# Rev_B.net
KiCad netlist of a schematic drawn in EAGLE
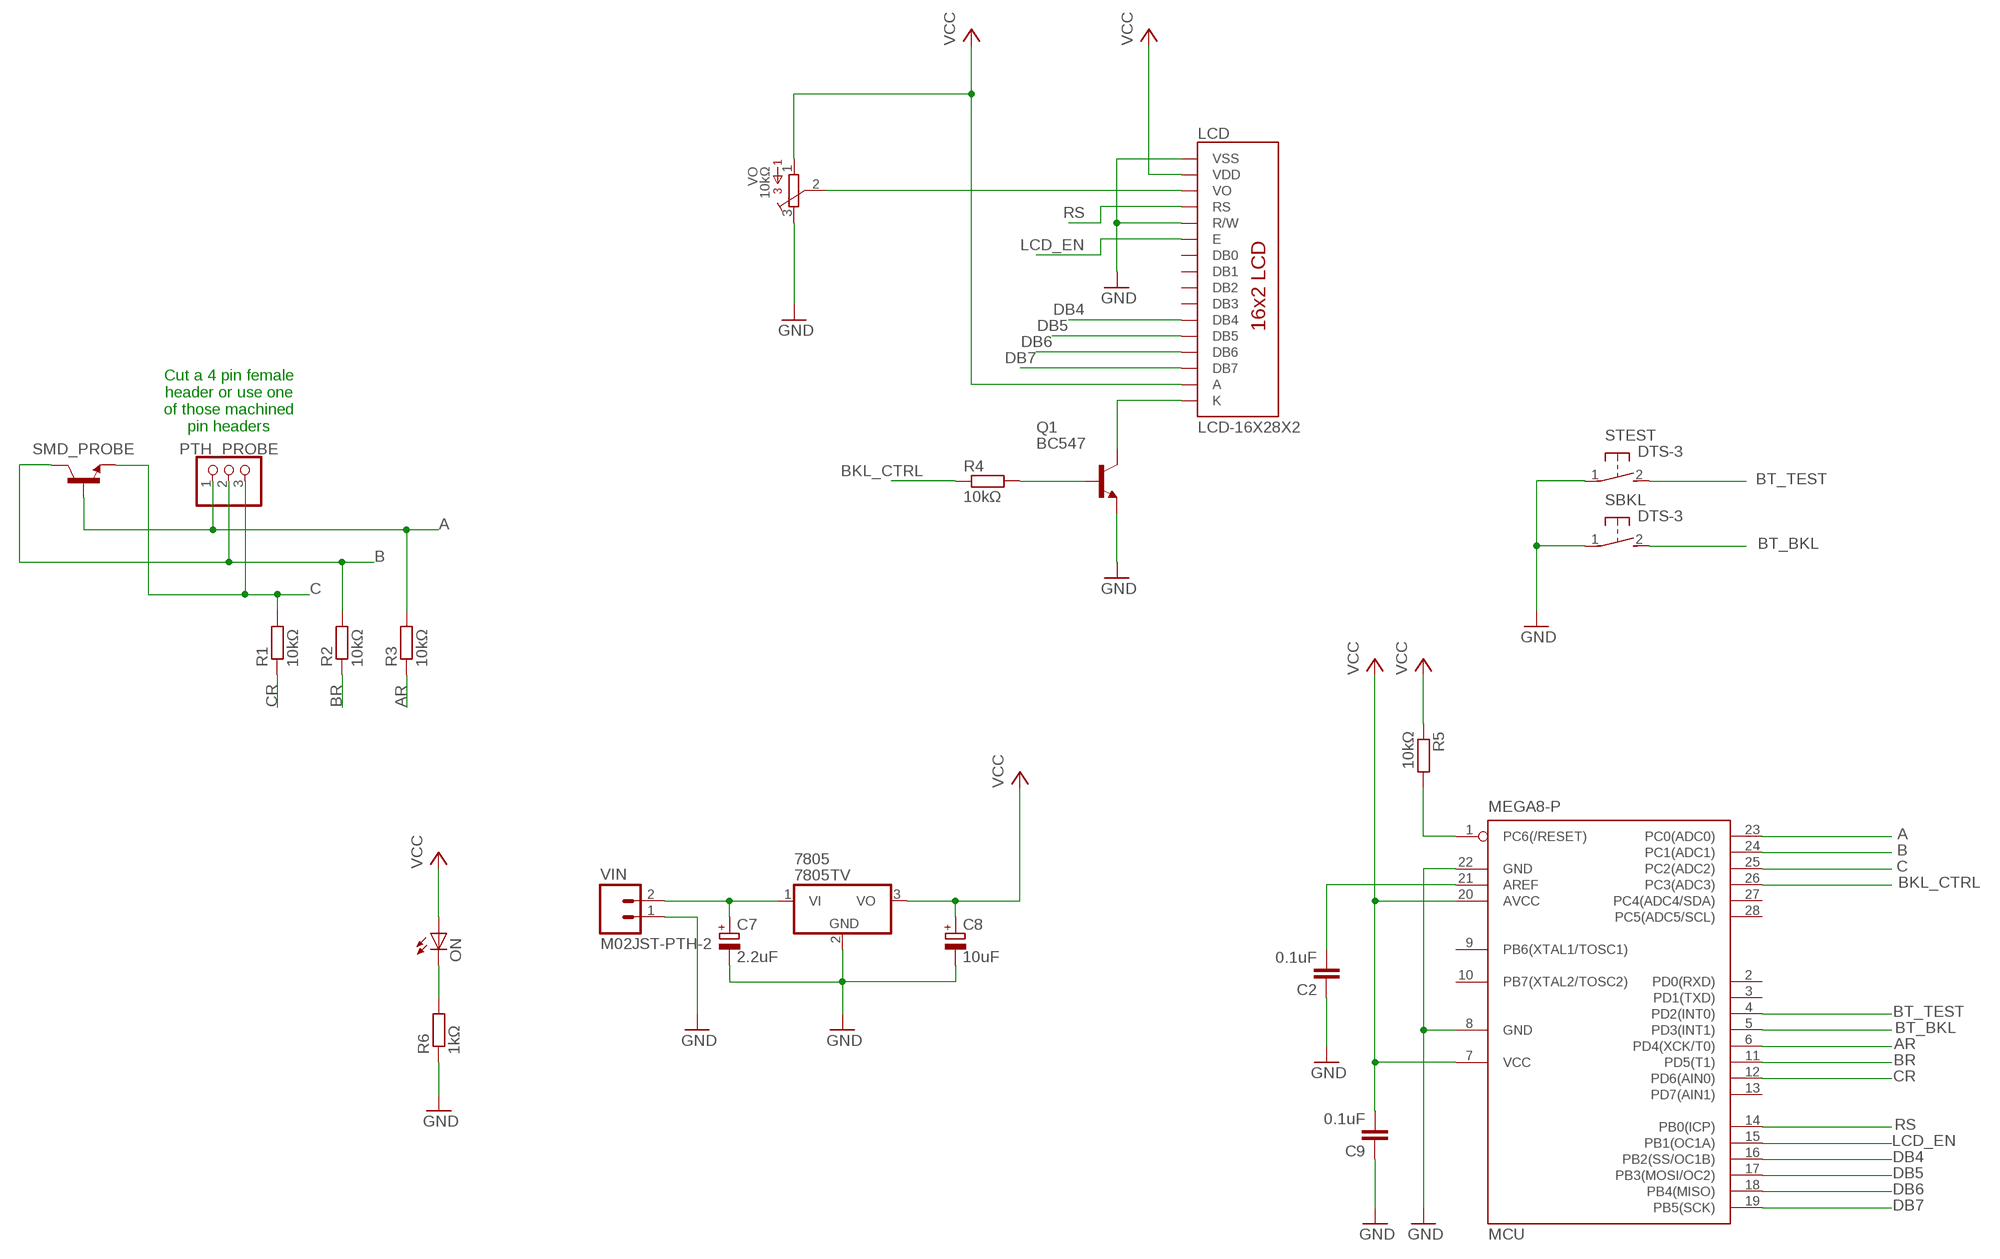
[diagram p0: schematic, sheet 1]

(export (version "E")
  (design (tool "Eeschema 10.0.6"))
  (components
    (comp (ref "7805")
      (value "7805TV")
      (footprint "eagle-import:TO220V")
      (libsource (lib "eagle-import") (part "78TV05"))
    )
    (comp (ref "C2")
      (value "0.1uF")
      (footprint "eagle-import:C025-025X050")
      (libsource (lib "eagle-import") (part "C-EU025-025X050"))
    )
    (comp (ref "C7")
      (value "2.2uF")
      (footprint "eagle-import:E2,5-6")
      (libsource (lib "eagle-import") (part "CPOL-EUE2.5-6"))
    )
    (comp (ref "C8")
      (value "10uF")
      (footprint "eagle-import:E2,5-6")
      (libsource (lib "eagle-import") (part "CPOL-EUE2.5-6"))
    )
    (comp (ref "C9")
      (value "0.1uF")
      (footprint "eagle-import:C050-025X075")
      (libsource (lib "eagle-import") (part "C-EU050-025X075"))
    )
    (comp (ref "LCD")
      (value "LCD-16X28X2")
      (footprint "eagle-import:LCD-8X2")
      (libsource (lib "eagle-import") (part "LCD-16X28X2"))
    )
    (comp (ref "MCU")
      (value "MEGA8-P")
      (footprint "eagle-import:DIL28-3")
      (libsource (lib "eagle-import") (part "MEGA8-P"))
    )
    (comp (ref "ON")
      (value "LED3MM")
      (footprint "eagle-import:LED3MM")
      (libsource (lib "eagle-import") (part "LED3MM"))
    )
    (comp (ref "PTH_PROBE")
      (value "PINHD-1X3")
      (footprint "eagle-import:1X03")
      (libsource (lib "eagle-import") (part "PINHD-1X3"))
    )
    (comp (ref "Q1")
      (value "BC547")
      (footprint "eagle-import:TO92")
      (libsource (lib "eagle-import") (part "BC547"))
    )
    (comp (ref "R1")
      (value "10kΩ")
      (footprint "eagle-import:0207_10")
      (libsource (lib "eagle-import") (part "resistor_R-EU_0207/10"))
    )
    (comp (ref "R2")
      (value "10kΩ")
      (footprint "eagle-import:0207_10")
      (libsource (lib "eagle-import") (part "resistor_R-EU_0207/10"))
    )
    (comp (ref "R3")
      (value "10kΩ")
      (footprint "eagle-import:0207_10")
      (libsource (lib "eagle-import") (part "resistor_R-EU_0207/10"))
    )
    (comp (ref "R4")
      (value "10kΩ")
      (footprint "eagle-import:0207_10")
      (libsource (lib "eagle-import") (part "R-EU_0207/10"))
    )
    (comp (ref "R5")
      (value "10kΩ")
      (footprint "eagle-import:0207_10")
      (libsource (lib "eagle-import") (part "R-EU_0207/10"))
    )
    (comp (ref "R6")
      (value "1kΩ")
      (footprint "eagle-import:0207_10")
      (libsource (lib "eagle-import") (part "R-EU_0207/10"))
    )
    (comp (ref "SBKL")
      (value "DTS-3")
      (footprint "eagle-import:DTS-3")
      (libsource (lib "eagle-import") (part "DTS-3"))
    )
    (comp (ref "SMD_PROBE")
      (value "BC817-25SMD")
      (footprint "eagle-import:SOT23-BEC")
      (libsource (lib "eagle-import") (part "BC817SMD-25"))
    )
    (comp (ref "STEST")
      (value "DTS-3")
      (footprint "eagle-import:DTS-3")
      (libsource (lib "eagle-import") (part "DTS-3"))
    )
    (comp (ref "VIN")
      (value "M02JST-PTH-2")
      (footprint "eagle-import:JST-2-PTH")
      (libsource (lib "eagle-import") (part "M02JST-PTH-2"))
    )
    (comp (ref "VO")
      (value "10kΩ")
      (footprint "eagle-import:3362H")
      (libsource (lib "eagle-import") (part "3362H"))
    )
  )
  (nets
    (net (code "1") (name "/A") (class "Default")
      (node (ref "MCU") (pin "23") (pinfunction "PC0(ADC0)_23") (pintype "bidirectional"))
      (node (ref "PTH_PROBE") (pin "1") (pinfunction "1_1") (pintype "passive"))
      (node (ref "R3") (pin "2") (pinfunction "2_2") (pintype "passive"))
      (node (ref "SMD_PROBE") (pin "B") (pinfunction "B_B") (pintype "passive"))
    )
    (net (code "2") (name "/AR") (class "Default")
      (node (ref "MCU") (pin "6") (pinfunction "PD4(XCK/T0)_6") (pintype "bidirectional"))
      (node (ref "R3") (pin "1") (pinfunction "1_1") (pintype "passive"))
    )
    (net (code "3") (name "/B") (class "Default")
      (node (ref "MCU") (pin "24") (pinfunction "PC1(ADC1)_24") (pintype "bidirectional"))
      (node (ref "PTH_PROBE") (pin "2") (pinfunction "2_2") (pintype "passive"))
      (node (ref "R2") (pin "2") (pinfunction "2_2") (pintype "passive"))
      (node (ref "SMD_PROBE") (pin "C") (pinfunction "C_C") (pintype "passive"))
    )
    (net (code "4") (name "/BKL_CTRL") (class "Default")
      (node (ref "MCU") (pin "26") (pinfunction "PC3(ADC3)_26") (pintype "bidirectional"))
      (node (ref "R4") (pin "1") (pinfunction "1_1") (pintype "passive"))
    )
    (net (code "5") (name "/BR") (class "Default")
      (node (ref "MCU") (pin "11") (pinfunction "PD5(T1)_11") (pintype "bidirectional"))
      (node (ref "R2") (pin "1") (pinfunction "1_1") (pintype "passive"))
    )
    (net (code "6") (name "/BT_BKL") (class "Default")
      (node (ref "MCU") (pin "5") (pinfunction "PD3(INT1)_5") (pintype "bidirectional"))
      (node (ref "SBKL") (pin "2") (pinfunction "2_2") (pintype "passive"))
    )
    (net (code "7") (name "/BT_TEST") (class "Default")
      (node (ref "MCU") (pin "4") (pinfunction "PD2(INT0)_4") (pintype "bidirectional"))
      (node (ref "STEST") (pin "2") (pinfunction "2_2") (pintype "passive"))
    )
    (net (code "8") (name "/C") (class "Default")
      (node (ref "MCU") (pin "25") (pinfunction "PC2(ADC2)_25") (pintype "bidirectional"))
      (node (ref "PTH_PROBE") (pin "3") (pinfunction "3_3") (pintype "passive"))
      (node (ref "R1") (pin "2") (pinfunction "2_2") (pintype "passive"))
      (node (ref "SMD_PROBE") (pin "E") (pinfunction "E_E") (pintype "passive"))
    )
    (net (code "9") (name "/CR") (class "Default")
      (node (ref "MCU") (pin "12") (pinfunction "PD6(AIN0)_12") (pintype "bidirectional"))
      (node (ref "R1") (pin "1") (pinfunction "1_1") (pintype "passive"))
    )
    (net (code "10") (name "/DB4") (class "Default")
      (node (ref "LCD") (pin "11") (pinfunction "DB4_11") (pintype "bidirectional"))
      (node (ref "MCU") (pin "16") (pinfunction "PB2(SS/OC1B)_16") (pintype "bidirectional"))
    )
    (net (code "11") (name "/DB5") (class "Default")
      (node (ref "LCD") (pin "12") (pinfunction "DB5_12") (pintype "bidirectional"))
      (node (ref "MCU") (pin "17") (pinfunction "PB3(MOSI/OC2)_17") (pintype "bidirectional"))
    )
    (net (code "12") (name "/DB6") (class "Default")
      (node (ref "LCD") (pin "13") (pinfunction "DB6_13") (pintype "bidirectional"))
      (node (ref "MCU") (pin "18") (pinfunction "PB4(MISO)_18") (pintype "bidirectional"))
    )
    (net (code "13") (name "/DB7") (class "Default")
      (node (ref "LCD") (pin "14") (pinfunction "DB7_14") (pintype "bidirectional"))
      (node (ref "MCU") (pin "19") (pinfunction "PB5(SCK)_19") (pintype "bidirectional"))
    )
    (net (code "14") (name "/LCD_EN") (class "Default")
      (node (ref "LCD") (pin "6") (pinfunction "E_6") (pintype "input"))
      (node (ref "MCU") (pin "15") (pinfunction "PB1(OC1A)_15") (pintype "bidirectional"))
    )
    (net (code "15") (name "/RS") (class "Default")
      (node (ref "LCD") (pin "4") (pinfunction "RS_4") (pintype "input"))
      (node (ref "MCU") (pin "14") (pinfunction "PB0(ICP)_14") (pintype "bidirectional"))
    )
    (net (code "16") (name "GND") (class "Default")
      (node (ref "7805") (pin "2") (pinfunction "GND_2") (pintype "passive"))
      (node (ref "C2") (pin "1") (pinfunction "1_1") (pintype "passive"))
      (node (ref "C7") (pin "-") (pinfunction "-_-") (pintype "passive"))
      (node (ref "C8") (pin "-") (pinfunction "-_-") (pintype "passive"))
      (node (ref "C9") (pin "1") (pinfunction "1_1") (pintype "passive"))
      (node (ref "LCD") (pin "1") (pinfunction "VSS_1") (pintype "power_in"))
      (node (ref "LCD") (pin "5") (pinfunction "R/W_5") (pintype "input"))
      (node (ref "MCU") (pin "22") (pinfunction "GND_22") (pintype "power_in"))
      (node (ref "MCU") (pin "8") (pinfunction "GND_8") (pintype "power_in"))
      (node (ref "Q1") (pin "1") (pinfunction "E_1") (pintype "passive"))
      (node (ref "R6") (pin "1") (pinfunction "1_1") (pintype "passive"))
      (node (ref "SBKL") (pin "1") (pinfunction "1_1") (pintype "passive"))
      (node (ref "STEST") (pin "1") (pinfunction "1_1") (pintype "passive"))
      (node (ref "VIN") (pin "1") (pinfunction "1_1") (pintype "passive"))
      (node (ref "VO") (pin "3") (pinfunction "3_3") (pintype "passive"))
    )
    (net (code "17") (name "Net-(7805-VI)") (class "Default")
      (node (ref "7805") (pin "1") (pinfunction "VI_1") (pintype "input"))
      (node (ref "C7") (pin "+") (pinfunction "+_+") (pintype "passive"))
      (node (ref "VIN") (pin "2") (pinfunction "2_2") (pintype "passive"))
    )
    (net (code "18") (name "Net-(LCD-K)") (class "Default")
      (node (ref "LCD") (pin "16") (pinfunction "K_16") (pintype "power_in"))
      (node (ref "Q1") (pin "3") (pinfunction "C_3") (pintype "passive"))
    )
    (net (code "19") (name "Net-(LCD-VO)") (class "Default")
      (node (ref "LCD") (pin "3") (pinfunction "VO_3") (pintype "bidirectional"))
      (node (ref "VO") (pin "2") (pinfunction "2_2") (pintype "passive"))
    )
    (net (code "20") (name "Net-(MCU-AREF)") (class "Default")
      (node (ref "C2") (pin "2") (pinfunction "2_2") (pintype "passive"))
      (node (ref "MCU") (pin "21") (pinfunction "AREF_21") (pintype "passive"))
    )
    (net (code "21") (name "Net-(MCU-PC6({slash}RESET))") (class "Default")
      (node (ref "MCU") (pin "1") (pinfunction "PC6(/RESET)_1") (pintype "bidirectional"))
      (node (ref "R5") (pin "2") (pinfunction "2_2") (pintype "passive"))
    )
    (net (code "22") (name "Net-(ON-C)") (class "Default")
      (node (ref "ON") (pin "K") (pinfunction "C_K") (pintype "passive"))
      (node (ref "R6") (pin "2") (pinfunction "2_2") (pintype "passive"))
    )
    (net (code "23") (name "Net-(Q1-B)") (class "Default")
      (node (ref "Q1") (pin "2") (pinfunction "B_2") (pintype "passive"))
      (node (ref "R4") (pin "2") (pinfunction "2_2") (pintype "passive"))
    )
    (net (code "24") (name "VCC") (class "Default")
      (node (ref "7805") (pin "3") (pinfunction "VO_3") (pintype "passive"))
      (node (ref "C8") (pin "+") (pinfunction "+_+") (pintype "passive"))
      (node (ref "C9") (pin "2") (pinfunction "2_2") (pintype "passive"))
      (node (ref "LCD") (pin "15") (pinfunction "A_15") (pintype "power_in"))
      (node (ref "LCD") (pin "2") (pinfunction "VDD_2") (pintype "power_in"))
      (node (ref "MCU") (pin "20") (pinfunction "AVCC_20") (pintype "power_in"))
      (node (ref "MCU") (pin "7") (pinfunction "VCC_7") (pintype "power_in"))
      (node (ref "ON") (pin "A") (pinfunction "A_A") (pintype "passive"))
      (node (ref "R5") (pin "1") (pinfunction "1_1") (pintype "passive"))
      (node (ref "VO") (pin "1") (pinfunction "1_1") (pintype "passive"))
    )
    (net (code "25") (name "unconnected-(LCD-DB0-Pad7)") (class "Default")
      (node (ref "LCD") (pin "7") (pinfunction "DB0_7") (pintype "bidirectional"))
    )
    (net (code "26") (name "unconnected-(LCD-DB1-Pad8)") (class "Default")
      (node (ref "LCD") (pin "8") (pinfunction "DB1_8") (pintype "bidirectional"))
    )
    (net (code "27") (name "unconnected-(LCD-DB2-Pad9)") (class "Default")
      (node (ref "LCD") (pin "9") (pinfunction "DB2_9") (pintype "bidirectional"))
    )
    (net (code "28") (name "unconnected-(LCD-DB3-Pad10)") (class "Default")
      (node (ref "LCD") (pin "10") (pinfunction "DB3_10") (pintype "bidirectional"))
    )
    (net (code "29") (name "unconnected-(MCU-PB6(XTAL1{slash}TOSC1)-Pad9)") (class "Default")
      (node (ref "MCU") (pin "9") (pinfunction "PB6(XTAL1/TOSC1)_9") (pintype "bidirectional"))
    )
    (net (code "30") (name "unconnected-(MCU-PB7(XTAL2{slash}TOSC2)-Pad10)") (class "Default")
      (node (ref "MCU") (pin "10") (pinfunction "PB7(XTAL2/TOSC2)_10") (pintype "bidirectional"))
    )
    (net (code "31") (name "unconnected-(MCU-PC4(ADC4{slash}SDA)-Pad27)") (class "Default")
      (node (ref "MCU") (pin "27") (pinfunction "PC4(ADC4/SDA)_27") (pintype "bidirectional"))
    )
    (net (code "32") (name "unconnected-(MCU-PC5(ADC5{slash}SCL)-Pad28)") (class "Default")
      (node (ref "MCU") (pin "28") (pinfunction "PC5(ADC5/SCL)_28") (pintype "bidirectional"))
    )
    (net (code "33") (name "unconnected-(MCU-PD0(RXD)-Pad2)") (class "Default")
      (node (ref "MCU") (pin "2") (pinfunction "PD0(RXD)_2") (pintype "bidirectional"))
    )
    (net (code "34") (name "unconnected-(MCU-PD1(TXD)-Pad3)") (class "Default")
      (node (ref "MCU") (pin "3") (pinfunction "PD1(TXD)_3") (pintype "bidirectional"))
    )
    (net (code "35") (name "unconnected-(MCU-PD7(AIN1)-Pad13)") (class "Default")
      (node (ref "MCU") (pin "13") (pinfunction "PD7(AIN1)_13") (pintype "bidirectional"))
    )
  )
)
